# MCU_Board.net
KiCad netlist of a schematic drawn in Altium Designer
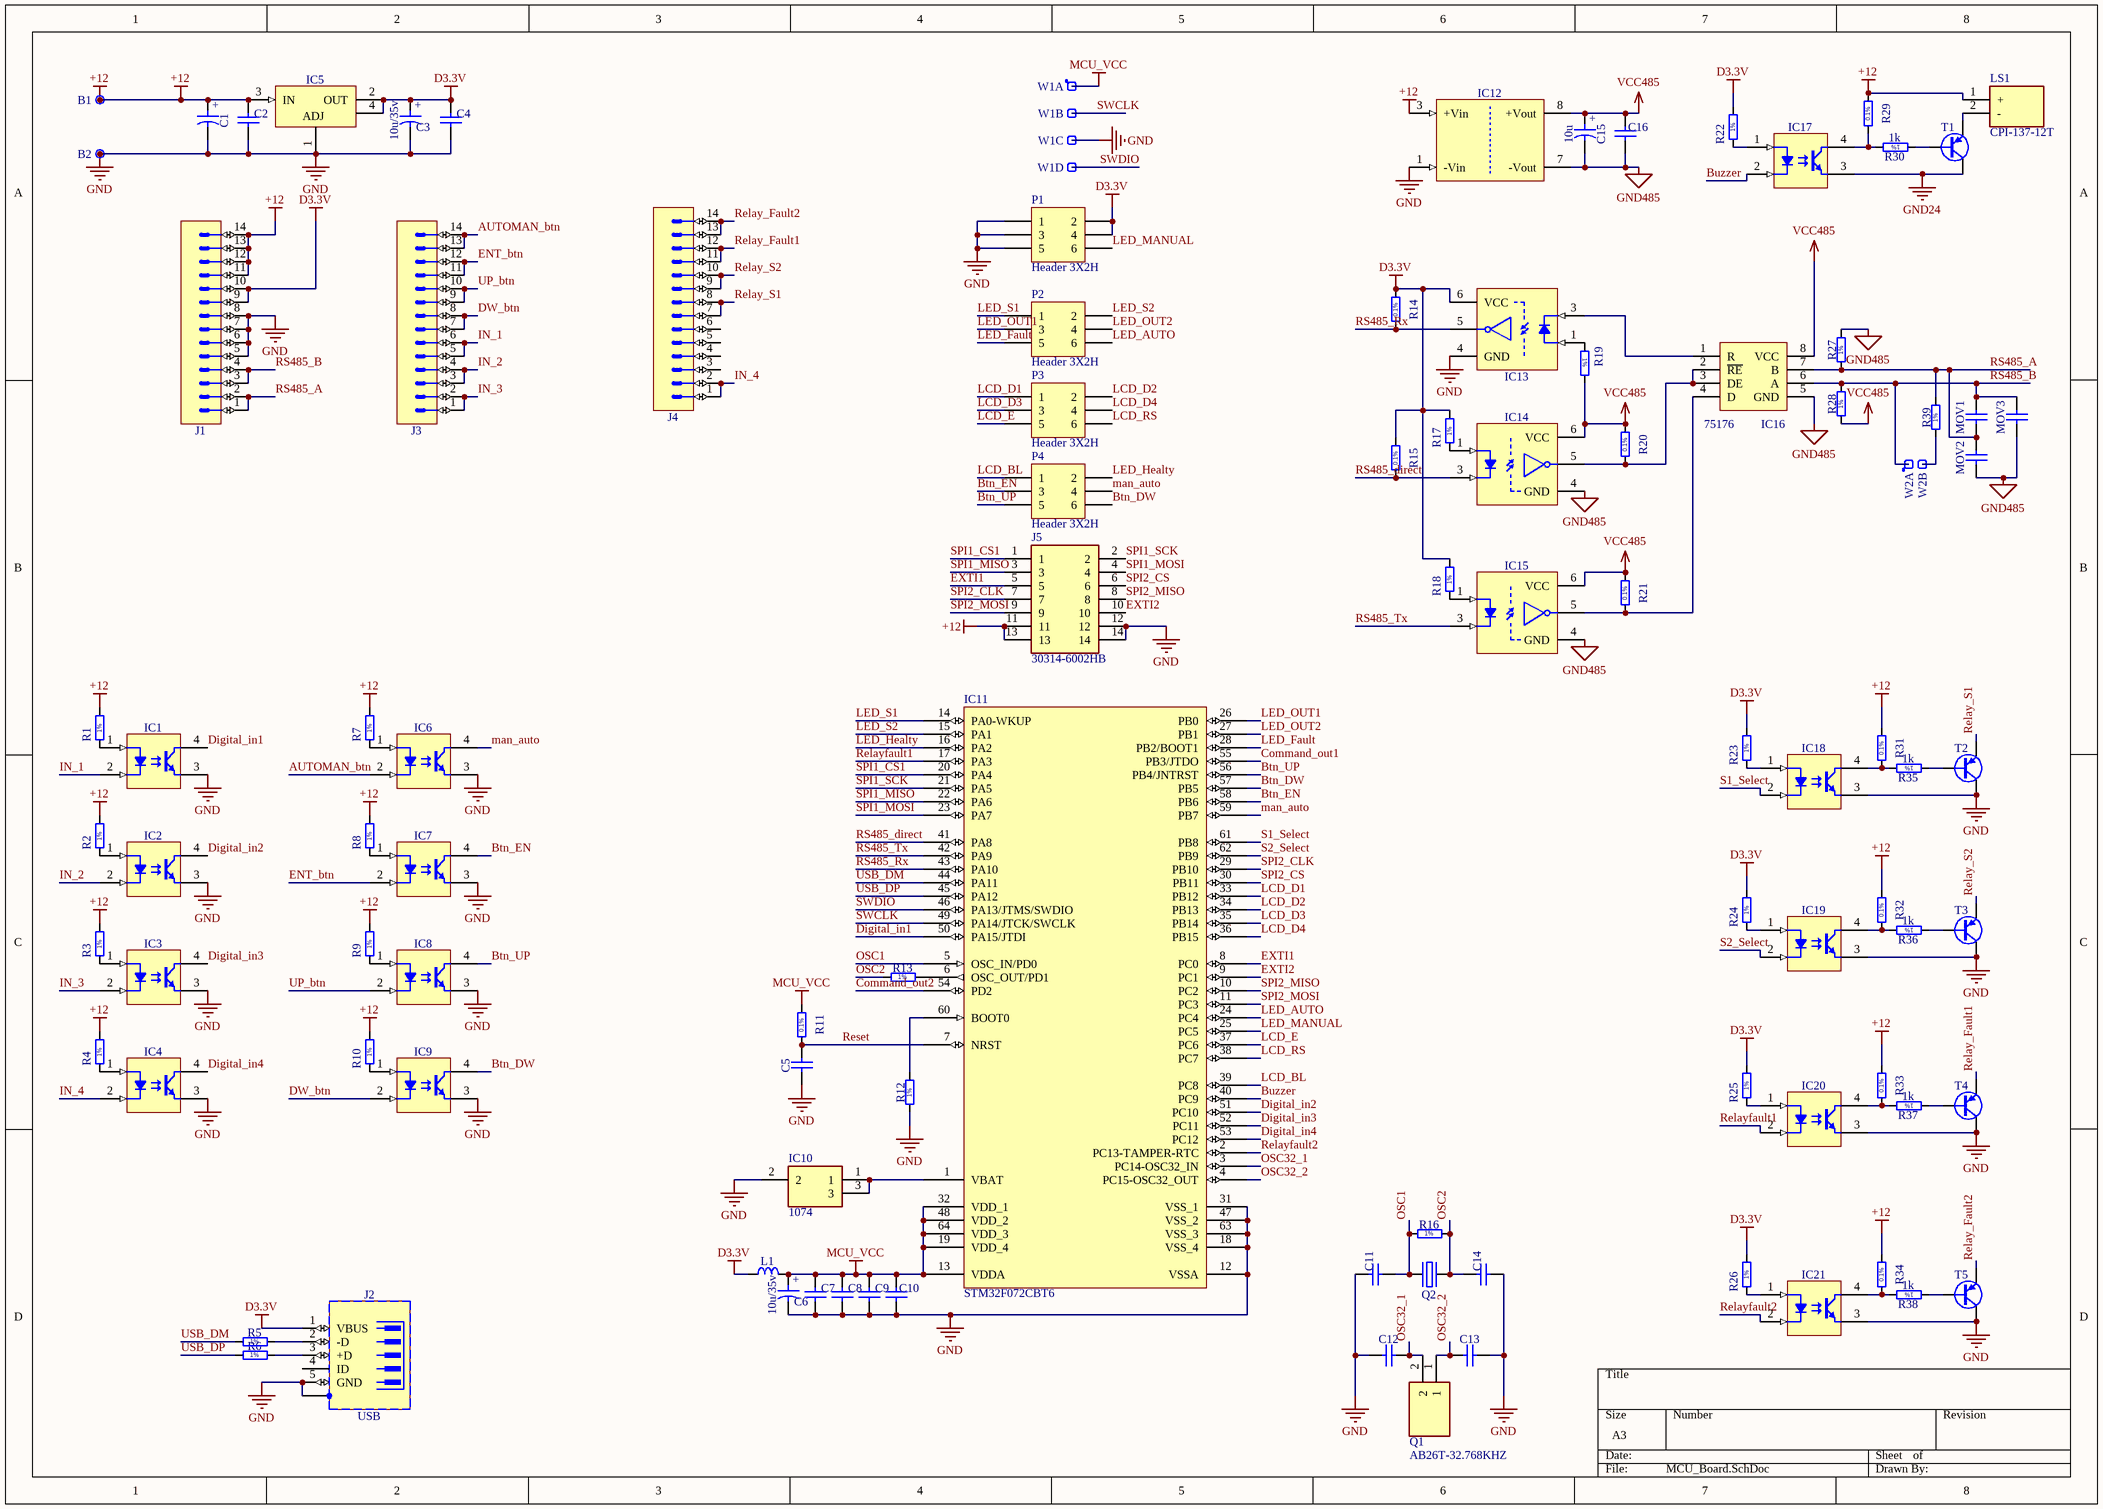
[diagram p0: MCU_Board.SchDoc]

(export (version "E")
  (design (tool "Eeschema 10.0.6"))
  (components
    (comp (ref "B1")
      (value "Plated Hole")
      (footprint "MTG240_400")
      (description "Single Terminal Socket")
      (fields (field (name "PART NUMBER") "PLATED_HOLE2.4_PAD4.0") (field (name "AUTHOR") "CERN DEM JMW"))
      (libsource (lib "Eletro-mechanical") (part "Single Terminal Socket"))
    )
    (comp (ref "B2")
      (value "Plated Hole")
      (footprint "MTG240_400")
      (description "Single Terminal Socket")
      (fields (field (name "PART NUMBER") "PLATED_HOLE2.4_PAD4.0") (field (name "AUTHOR") "CERN DEM JMW"))
      (libsource (lib "Eletro-mechanical") (part "Single Terminal Socket"))
    )
    (comp (ref "C1")
      (value "100uF")
      (footprint "CAPAE830X1020N")
      (description "Polarised capacitor")
      (fields
        (field (name "PART NUMBER") "CAE830-1020_100UF_35V_20%")
        (field (name "VOLTAGE") "35V")
        (field (name "AUTHOR") "CERN DEM JLC")
      )
      (libsource (lib "Capacitors") (part "Capacitor - polarized"))
    )
    (comp (ref "C2")
      (value "0.1uf")
      (footprint "CAPC2012X135N")
      (description "0092-0004-8")
      (fields
        (field (name "PART NUMBER") "CC0805_100NF_50V_10%_X7R")
        (field (name "VOLTAGE") "50V")
        (field (name "AUTHOR") "CERN DEM JLC")
      )
      (libsource (lib "Capacitors") (part "Capacitor - non polarized"))
    )
    (comp (ref "C3")
      (value "10u/35v")
      (footprint "CAPAE530X540N")
      (description "0289-0032-3")
      (fields
        (field (name "PART NUMBER") "CAE530-540_10UF_35V_20%")
        (field (name "VOLTAGE") "35V")
        (field (name "AUTHOR") "CERN DEM JLC")
      )
      (libsource (lib "Capacitors") (part "Capacitor - polarized"))
    )
    (comp (ref "C4")
      (value "0.1uf")
      (footprint "CAPC2012X135N")
      (description "0092-0004-8")
      (fields
        (field (name "PART NUMBER") "CC0805_100NF_50V_10%_X7R")
        (field (name "VOLTAGE") "50V")
        (field (name "AUTHOR") "CERN DEM JLC")
      )
      (libsource (lib "Capacitors") (part "Capacitor - non polarized"))
    )
    (comp (ref "C5")
      (value "0.1uf")
      (footprint "CAPC2012X135N")
      (description "0092-0004-8")
      (fields
        (field (name "PART NUMBER") "CC0805_100NF_50V_10%_X7R")
        (field (name "VOLTAGE") "50V")
        (field (name "AUTHOR") "CERN DEM JLC")
      )
      (libsource (lib "Capacitors") (part "Capacitor - non polarized"))
    )
    (comp (ref "C6")
      (value "10u/35v")
      (footprint "CAPAE530X540N")
      (description "0289-0032-3")
      (fields
        (field (name "PART NUMBER") "CAE530-540_10UF_35V_20%")
        (field (name "VOLTAGE") "35V")
        (field (name "AUTHOR") "CERN DEM JLC")
      )
      (libsource (lib "Capacitors") (part "Capacitor - polarized"))
    )
    (comp (ref "C7")
      (value "0.1uf")
      (footprint "CAPC2012X135N")
      (description "0092-0004-8")
      (fields
        (field (name "PART NUMBER") "CC0805_100NF_50V_10%_X7R")
        (field (name "VOLTAGE") "50V")
        (field (name "AUTHOR") "CERN DEM JLC")
      )
      (libsource (lib "Capacitors") (part "Capacitor - non polarized"))
    )
    (comp (ref "C8")
      (value "0.1uf")
      (footprint "CAPC2012X135N")
      (description "0092-0004-8")
      (fields
        (field (name "PART NUMBER") "CC0805_100NF_50V_10%_X7R")
        (field (name "VOLTAGE") "50V")
        (field (name "AUTHOR") "CERN DEM JLC")
      )
      (libsource (lib "Capacitors") (part "Capacitor - non polarized"))
    )
    (comp (ref "C9")
      (value "0.1uf")
      (footprint "CAPC2012X135N")
      (description "0092-0004-8")
      (fields
        (field (name "PART NUMBER") "CC0805_100NF_50V_10%_X7R")
        (field (name "VOLTAGE") "50V")
        (field (name "AUTHOR") "CERN DEM JLC")
      )
      (libsource (lib "Capacitors") (part "Capacitor - non polarized"))
    )
    (comp (ref "C10")
      (value "0.1uf")
      (footprint "CAPC2012X135N")
      (description "0092-0004-8")
      (fields
        (field (name "PART NUMBER") "CC0805_100NF_50V_10%_X7R")
        (field (name "VOLTAGE") "50V")
        (field (name "AUTHOR") "CERN DEM JLC")
      )
      (libsource (lib "Capacitors") (part "Capacitor - non polarized"))
    )
    (comp (ref "C11")
      (value "12pf")
      (footprint "CAPC2012X135N")
      (description "0306-0172-8")
      (fields
        (field (name "PART NUMBER") "CC0805_100NF_50V_10%_X7R")
        (field (name "VOLTAGE") "50V")
        (field (name "AUTHOR") "CERN DEM JLC")
      )
      (libsource (lib "Capacitors") (part "Capacitor - non polarized"))
    )
    (comp (ref "C12")
      (value "12pf")
      (footprint "CAPC2012X135N")
      (description "0306-0172-8")
      (fields
        (field (name "PART NUMBER") "CC0805_12PF_50V_5%_NP0")
        (field (name "VOLTAGE") "50V")
        (field (name "AUTHOR") "CERN DEM JLC")
      )
      (libsource (lib "Capacitors") (part "Capacitor - non polarized"))
    )
    (comp (ref "C13")
      (value "12pf")
      (footprint "CAPC2012X135N")
      (description "0306-0172-8")
      (fields
        (field (name "PART NUMBER") "CC0805_12PF_50V_5%_NP0")
        (field (name "VOLTAGE") "50V")
        (field (name "AUTHOR") "CERN DEM JLC")
      )
      (libsource (lib "Capacitors") (part "Capacitor - non polarized"))
    )
    (comp (ref "C14")
      (value "12pf")
      (footprint "CAPC2012X135N")
      (description "0306-0172-8")
      (fields
        (field (name "PART NUMBER") "CC0805_100NF_50V_10%_X7R")
        (field (name "VOLTAGE") "50V")
        (field (name "AUTHOR") "CERN DEM JLC")
      )
      (libsource (lib "Capacitors") (part "Capacitor - non polarized"))
    )
    (comp (ref "C15")
      (value "10u")
      (footprint "CAPAE430X540N")
      (description "0289-0167-5")
      (fields
        (field (name "PART NUMBER") "CAE430-540_10UF_16V_20%")
        (field (name "VOLTAGE") "16V")
        (field (name "AUTHOR") "CERN DEM JLC")
      )
      (libsource (lib "Capacitors") (part "Capacitor - polarized"))
    )
    (comp (ref "C16")
      (value "0.1uf")
      (footprint "CAPC2012X135N")
      (description "0092-0004-8")
      (fields
        (field (name "PART NUMBER") "CC0805_100NF_50V_10%_X7R")
        (field (name "VOLTAGE") "50V")
        (field (name "AUTHOR") "CERN DEM JLC")
      )
      (libsource (lib "Capacitors") (part "Capacitor - non polarized"))
    )
    (comp (ref "IC1")
      (value "PC817")
      (footprint "FAIRCHILD_FOD817DSD")
      (description "0084-0033-3")
      (fields
        (field (name "PART NUMBER") "FOD817DSD")
        (field (name "MANUFACTURER") "FAIRCHILD SEMICONDUCTOR")
        (field (name "AUTHOR") "CERN DEM JLC")
      )
      (libsource (lib "ICs And Semiconductors") (part "Optocoupler Type7"))
    )
    (comp (ref "IC2")
      (value "PC817")
      (footprint "FAIRCHILD_FOD817DSD")
      (description "0084-0033-3")
      (fields
        (field (name "PART NUMBER") "FOD817DSD")
        (field (name "MANUFACTURER") "FAIRCHILD SEMICONDUCTOR")
        (field (name "AUTHOR") "CERN DEM JLC")
      )
      (libsource (lib "ICs And Semiconductors") (part "Optocoupler Type7"))
    )
    (comp (ref "IC3")
      (value "PC817")
      (footprint "FAIRCHILD_FOD817DSD")
      (description "0084-0033-3")
      (fields
        (field (name "PART NUMBER") "FOD817DSD")
        (field (name "MANUFACTURER") "FAIRCHILD SEMICONDUCTOR")
        (field (name "AUTHOR") "CERN DEM JLC")
      )
      (libsource (lib "ICs And Semiconductors") (part "Optocoupler Type7"))
    )
    (comp (ref "IC4")
      (value "PC817")
      (footprint "FAIRCHILD_FOD817DSD")
      (description "0084-0033-3")
      (fields
        (field (name "PART NUMBER") "FOD817DSD")
        (field (name "MANUFACTURER") "FAIRCHILD SEMICONDUCTOR")
        (field (name "AUTHOR") "CERN DEM JLC")
      )
      (libsource (lib "ICs And Semiconductors") (part "Optocoupler Type7"))
    )
    (comp (ref "IC5")
      (value "LM1117MPX-3.3")
      (footprint "SOT230P700X180-4N")
      (description "0083-0491-4")
      (fields
        (field (name "PART NUMBER") "LM1117MPX-ADJ/NOPB")
        (field (name "MANUFACTURER") "NATIONAL SEMICONDUCTOR")
        (field (name "AUTHOR") "CERN DEM JLC")
      )
      (libsource (lib "ICs And Semiconductors") (part "REG3+1 1ADJ-2OUT-3IN+4OUT"))
    )
    (comp (ref "IC6")
      (value "PC817")
      (footprint "FAIRCHILD_FOD817DSD")
      (description "0084-0033-3")
      (fields
        (field (name "PART NUMBER") "FOD817DSD")
        (field (name "MANUFACTURER") "FAIRCHILD SEMICONDUCTOR")
        (field (name "AUTHOR") "CERN DEM JLC")
      )
      (libsource (lib "ICs And Semiconductors") (part "Optocoupler Type7"))
    )
    (comp (ref "IC7")
      (value "PC817")
      (footprint "FAIRCHILD_FOD817DSD")
      (description "0084-0033-3")
      (fields
        (field (name "PART NUMBER") "FOD817DSD")
        (field (name "MANUFACTURER") "FAIRCHILD SEMICONDUCTOR")
        (field (name "AUTHOR") "CERN DEM JLC")
      )
      (libsource (lib "ICs And Semiconductors") (part "Optocoupler Type7"))
    )
    (comp (ref "IC8")
      (value "PC817")
      (footprint "FAIRCHILD_FOD817DSD")
      (description "0084-0033-3")
      (fields
        (field (name "PART NUMBER") "FOD817DSD")
        (field (name "MANUFACTURER") "FAIRCHILD SEMICONDUCTOR")
        (field (name "AUTHOR") "CERN DEM JLC")
      )
      (libsource (lib "ICs And Semiconductors") (part "Optocoupler Type7"))
    )
    (comp (ref "IC9")
      (value "PC817")
      (footprint "FAIRCHILD_FOD817DSD")
      (description "0084-0033-3")
      (fields
        (field (name "PART NUMBER") "FOD817DSD")
        (field (name "MANUFACTURER") "FAIRCHILD SEMICONDUCTOR")
        (field (name "AUTHOR") "CERN DEM JLC")
      )
      (libsource (lib "ICs And Semiconductors") (part "Optocoupler Type7"))
    )
    (comp (ref "IC10")
      (value "1074")
      (footprint "SamacSys:1074")
      (description "Undefined or Miscellaneous")
      (fields (field (name "MOUSER2 PART NUMBER") "534-1074"))
      (libsource (lib "SamacSys") (part "1074"))
    )
    (comp (ref "IC11")
      (value "STM32F072CBT6")
      (footprint "LQFP64_N")
      (description "STM32 ARM-based 32-bit MCU with 64 Kbytes Flash, 64-pin LQFP, Industrial Temperature")
      (fields (field (name "PUBLISHER") "Altium Limited"))
      (libsource (lib "ST Microcontroller 32-Bit STM32") (part "STM32F103R8T6"))
    )
    (comp (ref "IC12")
      (value "TES 1-0511")
      (footprint "DCDC_TRACO_TES1-XX1X")
      (fields (field (name "MANUFACTURER") "TRACO POWER") (field (name "AUTHOR") "CERN DEM JMW"))
      (libsource (lib "ICs And Semiconductors") (part "DCDC_TRACO_TES1_Single Output"))
    )
    (comp (ref "IC13")
      (value "ACPL-W60L-000E")
      (footprint "SOIC127P1150X360-6N")
      (description "0087-0267-8")
      (fields (field (name "MANUFACTURER") "AVAGO TECHNOLOGIES") (field (name "AUTHOR") "CERN DEM JMW"))
      (libsource (lib "") (part "Optocoupler Type16_1"))
    )
    (comp (ref "IC14")
      (value "ACPL-W60L-000E")
      (footprint "SOIC127P1150X360-6N")
      (description "0087-0267-8")
      (fields (field (name "MANUFACTURER") "AVAGO TECHNOLOGIES") (field (name "AUTHOR") "CERN DEM JMW"))
      (libsource (lib "ICs And Semiconductors") (part "Optocoupler Type16"))
    )
    (comp (ref "IC15")
      (value "ACPL-W60L-000E")
      (footprint "SOIC127P1150X360-6N")
      (description "0087-0267-8")
      (fields (field (name "MANUFACTURER") "AVAGO TECHNOLOGIES") (field (name "AUTHOR") "CERN DEM JMW"))
      (libsource (lib "ICs And Semiconductors") (part "Optocoupler Type16"))
    )
    (comp (ref "IC16") (value "75176") (footprint "SO8_N") (libsource (lib "*") (part "SN75176")))
    (comp (ref "IC17")
      (value "PC817")
      (footprint "FAIRCHILD_FOD817DSD")
      (description "0084-0033-3")
      (fields
        (field (name "PART NUMBER") "FOD817DSD")
        (field (name "MANUFACTURER") "FAIRCHILD SEMICONDUCTOR")
        (field (name "AUTHOR") "CERN DEM JLC")
      )
      (libsource (lib "ICs And Semiconductors") (part "Optocoupler Type7"))
    )
    (comp (ref "IC18")
      (value "PC817")
      (footprint "FAIRCHILD_FOD817DSD")
      (description "0084-0033-3")
      (fields
        (field (name "PART NUMBER") "FOD817DSD")
        (field (name "MANUFACTURER") "FAIRCHILD SEMICONDUCTOR")
        (field (name "AUTHOR") "CERN DEM JLC")
      )
      (libsource (lib "ICs And Semiconductors") (part "Optocoupler Type7"))
    )
    (comp (ref "IC19")
      (value "PC817")
      (footprint "FAIRCHILD_FOD817DSD")
      (description "0084-0033-3")
      (fields
        (field (name "PART NUMBER") "FOD817DSD")
        (field (name "MANUFACTURER") "FAIRCHILD SEMICONDUCTOR")
        (field (name "AUTHOR") "CERN DEM JLC")
      )
      (libsource (lib "ICs And Semiconductors") (part "Optocoupler Type7"))
    )
    (comp (ref "IC20")
      (value "PC817")
      (footprint "FAIRCHILD_FOD817DSD")
      (description "0084-0033-3")
      (fields
        (field (name "PART NUMBER") "FOD817DSD")
        (field (name "MANUFACTURER") "FAIRCHILD SEMICONDUCTOR")
        (field (name "AUTHOR") "CERN DEM JLC")
      )
      (libsource (lib "ICs And Semiconductors") (part "Optocoupler Type7"))
    )
    (comp (ref "IC21")
      (value "PC817")
      (footprint "FAIRCHILD_FOD817DSD")
      (description "0084-0033-3")
      (fields
        (field (name "PART NUMBER") "FOD817DSD")
        (field (name "MANUFACTURER") "FAIRCHILD SEMICONDUCTOR")
        (field (name "AUTHOR") "CERN DEM JLC")
      )
      (libsource (lib "ICs And Semiconductors") (part "Optocoupler Type7"))
    )
    (comp (ref "J1")
      (value "Header 14")
      (footprint "STELVIO-KONTEK_3910401114400")
      (description "Connector 14 Male")
      (fields
        (field (name "PART NUMBER") "STELVIO-KONTEK_3910401114400")
        (field (name "MANUFACTURER") "STELVIO-KONTEK")
        (field (name "AUTHOR") "CERN DEM JLC")
      )
      (libsource (lib "Connectors") (part "Connector 14 Male"))
    )
    (comp (ref "J2")
      (value "USB")
      (footprint "TYCO_1734035-1")
      (description "5 Pin + 1 Shield USB Receptacle")
      (fields
        (field (name "PART NUMBER") "TYCO_1734035-1")
        (field (name "MANUFACTURER") "TYCO ELECTRONICS")
        (field (name "AUTHOR") "CERN DEM JLC")
      )
      (libsource (lib "Connectors") (part "Connector USB 5 Pin + 1Shield"))
    )
    (comp (ref "J3")
      (value "Header 14")
      (footprint "STELVIO-KONTEK_3910401114400")
      (description "Connector 14 Male")
      (fields
        (field (name "PART NUMBER") "STELVIO-KONTEK_3910401114400")
        (field (name "MANUFACTURER") "STELVIO-KONTEK")
        (field (name "AUTHOR") "CERN DEM JLC")
      )
      (libsource (lib "Connectors") (part "Connector 14 Male"))
    )
    (comp (ref "J4")
      (value "Header 14")
      (footprint "STELVIO-KONTEK_3910401114400")
      (description "Connector 14 Male")
      (fields
        (field (name "PART NUMBER") "STELVIO-KONTEK_3910401114400")
        (field (name "MANUFACTURER") "STELVIO-KONTEK")
        (field (name "AUTHOR") "CERN DEM JLC")
      )
      (libsource (lib "Connectors") (part "Connector 14 Male"))
    )
    (comp (ref "J5")
      (value "30314-6002HB")
      (footprint "SHDR14W64P254_2X7_2540X878X955P")
      (description "Connector")
      (libsource (lib "*") (part "30314-6002HB"))
    )
    (comp (ref "L1")
      (value "600")
      (footprint "INDC2012X105N")
      (description "0169-0010-4")
      (fields
        (field (name "PART NUMBER") "IND0805_MURATA_BLM21PG221SN1D")
        (field (name "POWER") "2A")
        (field (name "AUTHOR") "CERN DEM JLC")
      )
      (libsource (lib "Inductors & Transformers") (part "Inductor"))
    )
    (comp (ref "LS1")
      (value "CPI-137-12T")
      (footprint "SamacSys:CPI13712T")
      (description "Loudspeaker or Buzzer")
      (libsource (lib "SamacSys") (part "CPI-137-12T"))
    )
    (comp (ref "MOV1")
      (value "10nF")
      (footprint "CAPR500-300X720X650")
      (description "0221-0014-7")
      (fields
        (field (name "PART NUMBER") "CPER_10NF_400V_10%_500-300X720X650")
        (field (name "VOLTAGE") "400VDC/200VAC")
        (field (name "AUTHOR") "CERN DEM JLC")
      )
      (libsource (lib "Capacitors") (part "Capacitor - non polarized"))
    )
    (comp (ref "MOV2")
      (value "10nF")
      (footprint "CAPR500-300X720X650")
      (description "0221-0014-7")
      (fields
        (field (name "PART NUMBER") "CPER_10NF_400V_10%_500-300X720X650")
        (field (name "VOLTAGE") "400VDC/200VAC")
        (field (name "AUTHOR") "CERN DEM JLC")
      )
      (libsource (lib "Capacitors") (part "Capacitor - non polarized"))
    )
    (comp (ref "MOV3")
      (value "10nF")
      (footprint "CAPR500-300X720X650")
      (description "0221-0014-7")
      (fields
        (field (name "PART NUMBER") "CPER_10NF_400V_10%_500-300X720X650")
        (field (name "VOLTAGE") "400VDC/200VAC")
        (field (name "AUTHOR") "CERN DEM JLC")
      )
      (libsource (lib "Capacitors") (part "Capacitor - non polarized"))
    )
    (comp (ref "P1")
      (value "Header 3X2H")
      (footprint "HDR2X3H")
      (description "Header, 3-Pin, Dual row, Right Angle")
      (fields (field (name "PUBLISHER") "Altium Limited"))
      (libsource (lib "Miscellaneous Connectors") (part "Header 3X2H"))
    )
    (comp (ref "P2")
      (value "Header 3X2H")
      (footprint "HDR2X3H")
      (description "Header, 3-Pin, Dual row, Right Angle")
      (fields (field (name "PUBLISHER") "Altium Limited"))
      (libsource (lib "Miscellaneous Connectors") (part "Header 3X2H"))
    )
    (comp (ref "P3")
      (value "Header 3X2H")
      (footprint "HDR2X3H")
      (description "Header, 3-Pin, Dual row, Right Angle")
      (fields (field (name "PUBLISHER") "Altium Limited"))
      (libsource (lib "Miscellaneous Connectors") (part "Header 3X2H"))
    )
    (comp (ref "P4")
      (value "Header 3X2H")
      (footprint "HDR2X3H")
      (description "Header, 3-Pin, Dual row, Right Angle")
      (fields (field (name "PUBLISHER") "Altium Limited"))
      (libsource (lib "Miscellaneous Connectors") (part "Header 3X2H"))
    )
    (comp (ref "Q1")
      (value "AB26T-32.768KHZ")
      (footprint "SamacSys:AB26T")
      (description "Crystal or Oscillator")
      (libsource (lib "SamacSys") (part "AB26T-32.768KHZ"))
    )
    (comp (ref "Q2")
      (value "8.192Mhz")
      (footprint "XTAL1160X490X430")
      (description "No E -source")
      (fields
        (field (name "PART NUMBER") "XTAL_6MHZ_RAKON_HC49/4H SMX_20/50/10/16")
        (field (name "MANUFACTURER") "RAKON")
        (field (name "AUTHOR") "CERN DEM JMW")
      )
      (libsource (lib "ICs And Semiconductors") (part "Quartz Crystal"))
    )
    (comp (ref "R1")
      (value "330")
      (footprint "RESC2012X60N")
      (description "0150-3297-4")
      (fields
        (field (name "PART NUMBER") "R0805_330R_1%_0.125W_100PPM")
        (field (name "POWER") "0.125W")
        (field (name "AUTHOR") "CERN DEM JLC")
      )
      (libsource (lib "Resistors") (part "Resistor - 1%"))
    )
    (comp (ref "R2")
      (value "330")
      (footprint "RESC2012X60N")
      (description "0150-3297-4")
      (fields
        (field (name "PART NUMBER") "R0805_330R_1%_0.125W_100PPM")
        (field (name "POWER") "0.125W")
        (field (name "AUTHOR") "CERN DEM JLC")
      )
      (libsource (lib "Resistors") (part "Resistor - 1%"))
    )
    (comp (ref "R3")
      (value "330")
      (footprint "RESC2012X60N")
      (description "0150-3297-4")
      (fields
        (field (name "PART NUMBER") "R0805_330R_1%_0.125W_100PPM")
        (field (name "POWER") "0.125W")
        (field (name "AUTHOR") "CERN DEM JLC")
      )
      (libsource (lib "Resistors") (part "Resistor - 1%"))
    )
    (comp (ref "R4")
      (value "330")
      (footprint "RESC2012X60N")
      (description "0150-3297-4")
      (fields
        (field (name "PART NUMBER") "R0805_330R_1%_0.125W_100PPM")
        (field (name "POWER") "0.125W")
        (field (name "AUTHOR") "CERN DEM JLC")
      )
      (libsource (lib "Resistors") (part "Resistor - 1%"))
    )
    (comp (ref "R5")
      (value "27")
      (footprint "RESC2012X60N")
      (description "Resistor - 1%")
      (fields
        (field (name "PART NUMBER") "R0805_27R_1%_0.125W_100PPM")
        (field (name "POWER") "0.125W")
        (field (name "AUTHOR") "CERN DEM JLC")
      )
      (libsource (lib "Resistors") (part "Resistor - 1%"))
    )
    (comp (ref "R6")
      (value "27")
      (footprint "RESC2012X60N")
      (description "Resistor - 1%")
      (fields
        (field (name "PART NUMBER") "R0805_27R_1%_0.125W_100PPM")
        (field (name "POWER") "0.125W")
        (field (name "AUTHOR") "CERN DEM JLC")
      )
      (libsource (lib "Resistors") (part "Resistor - 1%"))
    )
    (comp (ref "R7")
      (value "330")
      (footprint "RESC2012X60N")
      (description "0150-3297-4")
      (fields
        (field (name "PART NUMBER") "R0805_330R_1%_0.125W_100PPM")
        (field (name "POWER") "0.125W")
        (field (name "AUTHOR") "CERN DEM JLC")
      )
      (libsource (lib "Resistors") (part "Resistor - 1%"))
    )
    (comp (ref "R8")
      (value "330")
      (footprint "RESC2012X60N")
      (description "0150-3297-4")
      (fields
        (field (name "PART NUMBER") "R0805_330R_1%_0.125W_100PPM")
        (field (name "POWER") "0.125W")
        (field (name "AUTHOR") "CERN DEM JLC")
      )
      (libsource (lib "Resistors") (part "Resistor - 1%"))
    )
    (comp (ref "R9")
      (value "330")
      (footprint "RESC2012X60N")
      (description "0150-3297-4")
      (fields
        (field (name "PART NUMBER") "R0805_330R_1%_0.125W_100PPM")
        (field (name "POWER") "0.125W")
        (field (name "AUTHOR") "CERN DEM JLC")
      )
      (libsource (lib "Resistors") (part "Resistor - 1%"))
    )
    (comp (ref "R10")
      (value "330")
      (footprint "RESC2012X60N")
      (description "0150-3297-4")
      (fields
        (field (name "PART NUMBER") "R0805_330R_1%_0.125W_100PPM")
        (field (name "POWER") "0.125W")
        (field (name "AUTHOR") "CERN DEM JLC")
      )
      (libsource (lib "Resistors") (part "Resistor - 1%"))
    )
    (comp (ref "R11")
      (value "10k")
      (footprint "RESC2012X60N")
      (description "0176-0426-3")
      (fields
        (field (name "PART NUMBER") "R0805_10K_0.1%_0.1W_10PPM")
        (field (name "POWER") "0.1W")
        (field (name "AUTHOR") "CERN DEM JLC")
      )
      (libsource (lib "Resistors") (part "Resistor - 0.1%"))
    )
    (comp (ref "R12")
      (value "510")
      (footprint "RESC2012X60N")
      (description "Resistor - 1%")
      (fields
        (field (name "PART NUMBER") "R0805_510R_1%_0.125W_100PPM")
        (field (name "POWER") "0.125W")
        (field (name "AUTHOR") "CERN DEM JLC")
      )
      (libsource (lib "Resistors") (part "Resistor - 1%"))
    )
    (comp (ref "R13")
      (value "220")
      (footprint "RESC2012X60N")
      (description "Resistor - 1%")
      (fields
        (field (name "PART NUMBER") "R0805_220R_1%_0.125W_100PPM")
        (field (name "POWER") "0.125W")
        (field (name "AUTHOR") "CERN DEM JLC")
      )
      (libsource (lib "Resistors") (part "Resistor - 1%"))
    )
    (comp (ref "R14")
      (value "10k")
      (footprint "RESC2012X60N")
      (description "0176-0426-3")
      (fields
        (field (name "PART NUMBER") "R0805_10K_0.1%_0.1W_10PPM")
        (field (name "POWER") "0.1W")
        (field (name "AUTHOR") "CERN DEM JLC")
      )
      (libsource (lib "Resistors") (part "Resistor - 0.1%"))
    )
    (comp (ref "R15")
      (value "10k")
      (footprint "RESC2012X60N")
      (description "0176-0426-3")
      (fields
        (field (name "PART NUMBER") "R0805_10K_0.1%_0.1W_10PPM")
        (field (name "POWER") "0.1W")
        (field (name "AUTHOR") "CERN DEM JLC")
      )
      (libsource (lib "Resistors") (part "Resistor - 0.1%"))
    )
    (comp (ref "R16")
      (value "1M")
      (footprint "RESC2012X60N")
      (description "Resistor - 1%")
      (fields
        (field (name "PART NUMBER") "R0805_1M_1%_0.125W_100PPM")
        (field (name "POWER") "0.125W")
        (field (name "AUTHOR") "CERN DEM JLC")
      )
      (libsource (lib "Resistors") (part "Resistor - 1%"))
    )
    (comp (ref "R17")
      (value "330")
      (footprint "RESC2012X60N")
      (description "0150-3297-4")
      (fields
        (field (name "PART NUMBER") "R0805_330R_1%_0.125W_100PPM")
        (field (name "POWER") "0.125W")
        (field (name "AUTHOR") "CERN DEM JLC")
      )
      (libsource (lib "Resistors") (part "Resistor - 1%"))
    )
    (comp (ref "R18")
      (value "330")
      (footprint "RESC2012X60N")
      (description "0150-3297-4")
      (fields
        (field (name "PART NUMBER") "R0805_330R_1%_0.125W_100PPM")
        (field (name "POWER") "0.125W")
        (field (name "AUTHOR") "CERN DEM JLC")
      )
      (libsource (lib "Resistors") (part "Resistor - 1%"))
    )
    (comp (ref "R19")
      (value "330")
      (footprint "RESC2012X60N")
      (description "0150-3297-4")
      (fields
        (field (name "PART NUMBER") "R0805_330R_1%_0.125W_100PPM")
        (field (name "POWER") "0.125W")
        (field (name "AUTHOR") "CERN DEM JLC")
      )
      (libsource (lib "Resistors") (part "Resistor - 1%"))
    )
    (comp (ref "R20")
      (value "10k")
      (footprint "RESC2012X60N")
      (description "0176-0426-3")
      (fields
        (field (name "PART NUMBER") "R0805_10K_0.1%_0.1W_10PPM")
        (field (name "POWER") "0.1W")
        (field (name "AUTHOR") "CERN DEM JLC")
      )
      (libsource (lib "Resistors") (part "Resistor - 0.1%"))
    )
    (comp (ref "R21")
      (value "10k")
      (footprint "RESC2012X60N")
      (description "0176-0426-3")
      (fields
        (field (name "PART NUMBER") "R0805_10K_0.1%_0.1W_10PPM")
        (field (name "POWER") "0.1W")
        (field (name "AUTHOR") "CERN DEM JLC")
      )
      (libsource (lib "Resistors") (part "Resistor - 0.1%"))
    )
    (comp (ref "R22")
      (value "330")
      (footprint "RESC2012X60N")
      (description "0150-3297-4")
      (fields
        (field (name "PART NUMBER") "R0805_330R_1%_0.125W_100PPM")
        (field (name "POWER") "0.125W")
        (field (name "AUTHOR") "CERN DEM JLC")
      )
      (libsource (lib "Resistors") (part "Resistor - 1%"))
    )
    (comp (ref "R23")
      (value "330")
      (footprint "RESC2012X60N")
      (description "0150-3297-4")
      (fields
        (field (name "PART NUMBER") "R0805_330R_1%_0.125W_100PPM")
        (field (name "POWER") "0.125W")
        (field (name "AUTHOR") "CERN DEM JLC")
      )
      (libsource (lib "Resistors") (part "Resistor - 1%"))
    )
    (comp (ref "R24")
      (value "330")
      (footprint "RESC2012X60N")
      (description "0150-3297-4")
      (fields
        (field (name "PART NUMBER") "R0805_330R_1%_0.125W_100PPM")
        (field (name "POWER") "0.125W")
        (field (name "AUTHOR") "CERN DEM JLC")
      )
      (libsource (lib "Resistors") (part "Resistor - 1%"))
    )
    (comp (ref "R25")
      (value "330")
      (footprint "RESC2012X60N")
      (description "0150-3297-4")
      (fields
        (field (name "PART NUMBER") "R0805_330R_1%_0.125W_100PPM")
        (field (name "POWER") "0.125W")
        (field (name "AUTHOR") "CERN DEM JLC")
      )
      (libsource (lib "Resistors") (part "Resistor - 1%"))
    )
    (comp (ref "R26")
      (value "330")
      (footprint "RESC2012X60N")
      (description "0150-3297-4")
      (fields
        (field (name "PART NUMBER") "R0805_330R_1%_0.125W_100PPM")
        (field (name "POWER") "0.125W")
        (field (name "AUTHOR") "CERN DEM JLC")
      )
      (libsource (lib "Resistors") (part "Resistor - 1%"))
    )
    (comp (ref "R27")
      (value "20k")
      (footprint "RESC2012X60N")
      (description "0176-0560-6")
      (fields
        (field (name "PART NUMBER") "R0805_20K_1%_0.125W_100PPM")
        (field (name "POWER") "0.125W")
        (field (name "AUTHOR") "CERN DEM JLC")
      )
      (libsource (lib "Resistors") (part "Resistor - 1%"))
    )
    (comp (ref "R28")
      (value "20k")
      (footprint "RESC2012X60N")
      (description "0176-0560-6")
      (fields
        (field (name "PART NUMBER") "R0805_20K_1%_0.125W_100PPM")
        (field (name "POWER") "0.125W")
        (field (name "AUTHOR") "CERN DEM JLC")
      )
      (libsource (lib "Resistors") (part "Resistor - 1%"))
    )
    (comp (ref "R29")
      (value "10k")
      (footprint "RESC2012X60N")
      (description "0176-0426-3")
      (fields
        (field (name "PART NUMBER") "R0805_10K_0.1%_0.1W_10PPM")
        (field (name "POWER") "0.1W")
        (field (name "AUTHOR") "CERN DEM JLC")
      )
      (libsource (lib "Resistors") (part "Resistor - 0.1%"))
    )
    (comp (ref "R30")
      (value "1k")
      (footprint "RESC2012X60N")
      (description "0176-0313-5")
      (fields
        (field (name "PART NUMBER") "R0805_1K_1%_0.125W_100PPM")
        (field (name "POWER") "0.125W")
        (field (name "AUTHOR") "CERN DEM JLC")
      )
      (libsource (lib "Resistors") (part "Resistor - 1%"))
    )
    (comp (ref "R31")
      (value "10k")
      (footprint "RESC2012X60N")
      (description "0176-0426-3")
      (fields
        (field (name "PART NUMBER") "R0805_10K_0.1%_0.1W_10PPM")
        (field (name "POWER") "0.1W")
        (field (name "AUTHOR") "CERN DEM JLC")
      )
      (libsource (lib "Resistors") (part "Resistor - 0.1%"))
    )
    (comp (ref "R32")
      (value "10k")
      (footprint "RESC2012X60N")
      (description "0176-0426-3")
      (fields
        (field (name "PART NUMBER") "R0805_10K_0.1%_0.1W_10PPM")
        (field (name "POWER") "0.1W")
        (field (name "AUTHOR") "CERN DEM JLC")
      )
      (libsource (lib "Resistors") (part "Resistor - 0.1%"))
    )
    (comp (ref "R33")
      (value "10k")
      (footprint "RESC2012X60N")
      (description "0176-0426-3")
      (fields
        (field (name "PART NUMBER") "R0805_10K_0.1%_0.1W_10PPM")
        (field (name "POWER") "0.1W")
        (field (name "AUTHOR") "CERN DEM JLC")
      )
      (libsource (lib "Resistors") (part "Resistor - 0.1%"))
    )
    (comp (ref "R34")
      (value "10k")
      (footprint "RESC2012X60N")
      (description "0176-0426-3")
      (fields
        (field (name "PART NUMBER") "R0805_10K_0.1%_0.1W_10PPM")
        (field (name "POWER") "0.1W")
        (field (name "AUTHOR") "CERN DEM JLC")
      )
      (libsource (lib "Resistors") (part "Resistor - 0.1%"))
    )
    (comp (ref "R35")
      (value "1k")
      (footprint "RESC2012X60N")
      (description "0176-0313-5")
      (fields
        (field (name "PART NUMBER") "R0805_1K_1%_0.125W_100PPM")
        (field (name "POWER") "0.125W")
        (field (name "AUTHOR") "CERN DEM JLC")
      )
      (libsource (lib "Resistors") (part "Resistor - 1%"))
    )
    (comp (ref "R36")
      (value "1k")
      (footprint "RESC2012X60N")
      (description "0176-0313-5")
      (fields
        (field (name "PART NUMBER") "R0805_1K_1%_0.125W_100PPM")
        (field (name "POWER") "0.125W")
        (field (name "AUTHOR") "CERN DEM JLC")
      )
      (libsource (lib "Resistors") (part "Resistor - 1%"))
    )
    (comp (ref "R37")
      (value "1k")
      (footprint "RESC2012X60N")
      (description "0176-0313-5")
      (fields
        (field (name "PART NUMBER") "R0805_1K_1%_0.125W_100PPM")
        (field (name "POWER") "0.125W")
        (field (name "AUTHOR") "CERN DEM JLC")
      )
      (libsource (lib "Resistors") (part "Resistor - 1%"))
    )
    (comp (ref "R38")
      (value "1k")
      (footprint "RESC2012X60N")
      (description "0176-0313-5")
      (fields
        (field (name "PART NUMBER") "R0805_1K_1%_0.125W_100PPM")
        (field (name "POWER") "0.125W")
        (field (name "AUTHOR") "CERN DEM JLC")
      )
      (libsource (lib "Resistors") (part "Resistor - 1%"))
    )
    (comp (ref "R39")
      (value "120")
      (footprint "RESC1608X55N")
      (description "0150-2451-4")
      (fields
        (field (name "PART NUMBER") "R0603_120R_1%_0.1W_100PPM")
        (field (name "POWER") "0.1W")
        (field (name "AUTHOR") "CERN DEM JLC")
      )
      (libsource (lib "Resistors") (part "Resistor - 1%"))
    )
    (comp (ref "T1")
      (value "MMBT3906LT1G")
      (footprint "SOT95P240X110-3N")
      (description "0235-0223-4")
      (fields
        (field (name "PART NUMBER") "BSR18A")
        (field (name "MANUFACTURER") "FAIRCHILD SEMICONDUCTOR")
        (field (name "AUTHOR") "CERN DEM JLC")
      )
      (libsource (lib "ICs And Semiconductors") (part "PNP B1 E2 C3"))
    )
    (comp (ref "T2")
      (value "MMBT3906LT1G")
      (footprint "SOT95P240X110-3N")
      (description "0235-0223-4")
      (fields
        (field (name "PART NUMBER") "BSR18A")
        (field (name "MANUFACTURER") "FAIRCHILD SEMICONDUCTOR")
        (field (name "AUTHOR") "CERN DEM JLC")
      )
      (libsource (lib "ICs And Semiconductors") (part "PNP B1 E2 C3"))
    )
    (comp (ref "T3")
      (value "MMBT3906LT1G")
      (footprint "SOT95P240X110-3N")
      (description "0235-0223-4")
      (fields
        (field (name "PART NUMBER") "BSR18A")
        (field (name "MANUFACTURER") "FAIRCHILD SEMICONDUCTOR")
        (field (name "AUTHOR") "CERN DEM JLC")
      )
      (libsource (lib "ICs And Semiconductors") (part "PNP B1 E2 C3"))
    )
    (comp (ref "T4")
      (value "MMBT3906LT1G")
      (footprint "SOT95P240X110-3N")
      (description "0235-0223-4")
      (fields
        (field (name "PART NUMBER") "BSR18A")
        (field (name "MANUFACTURER") "FAIRCHILD SEMICONDUCTOR")
        (field (name "AUTHOR") "CERN DEM JLC")
      )
      (libsource (lib "ICs And Semiconductors") (part "PNP B1 E2 C3"))
    )
    (comp (ref "T5")
      (value "MMBT3906LT1G")
      (footprint "SOT95P240X110-3N")
      (description "0235-0223-4")
      (fields
        (field (name "PART NUMBER") "BSR18A")
        (field (name "MANUFACTURER") "FAIRCHILD SEMICONDUCTOR")
        (field (name "AUTHOR") "CERN DEM JLC")
      )
      (libsource (lib "ICs And Semiconductors") (part "PNP B1 E2 C3"))
    )
    (comp (ref "W1")
      (value "Test Point")
      (footprint "COMATEL_385.0358.1.04.400")
      (description "4 Mini Wire-Wrap Contact Strip Header")
      (fields
        (field (name "PART NUMBER") "COMATEL_385.0358.1.04.400")
        (field (name "MANUFACTURER") "KONTEK COMATEL")
        (field (name "AUTHOR") "CERN DEM JLC")
      )
      (libsource (lib "Connectors") (part "Wire-Wrap Contact x4"))
    )
    (comp (ref "W2")
      (value "Test Point")
      (footprint "COMATEL_386.0358.1.02.440")
      (description "2 Mini Wire-Wrap Contact Strip Header")
      (fields
        (field (name "PART NUMBER") "COMATEL_386.0358.1.02.440")
        (field (name "MANUFACTURER") "KONTEK COMATEL")
        (field (name "AUTHOR") "CERN DEM JLC")
      )
      (libsource (lib "Connectors") (part "Wire-Wrap Contact x2"))
    )
  )
  (nets
    (net (code "1") (name "+12") (class "Default")
      (node (ref "B1") (pin "1") (pinfunction "1_1") (pintype "bidirectional"))
      (node (ref "C1") (pin "1") (pinfunction "1_1") (pintype "passive"))
      (node (ref "C2") (pin "1") (pinfunction "1_1") (pintype "passive"))
      (node (ref "IC12") (pin "3") (pinfunction "+Vin_3") (pintype "input"))
      (node (ref "IC5") (pin "3") (pinfunction "IN_3") (pintype "input"))
      (node (ref "J1") (pin "11") (pinfunction "11_11") (pintype "bidirectional"))
      (node (ref "J1") (pin "12") (pinfunction "12_12") (pintype "bidirectional"))
      (node (ref "J1") (pin "13") (pinfunction "13_13") (pintype "bidirectional"))
      (node (ref "J1") (pin "14") (pinfunction "14_14") (pintype "bidirectional"))
      (node (ref "J5") (pin "11") (pinfunction "11_11") (pintype "passive"))
      (node (ref "J5") (pin "13") (pinfunction "13_13") (pintype "passive"))
      (node (ref "LS1") (pin "1") (pinfunction "+_1") (pintype "passive"))
      (node (ref "R1") (pin "2") (pinfunction "2_2") (pintype "passive"))
      (node (ref "R10") (pin "2") (pinfunction "2_2") (pintype "passive"))
      (node (ref "R2") (pin "2") (pinfunction "2_2") (pintype "passive"))
      (node (ref "R29") (pin "2") (pinfunction "2_2") (pintype "passive"))
      (node (ref "R3") (pin "2") (pinfunction "2_2") (pintype "passive"))
      (node (ref "R31") (pin "2") (pinfunction "2_2") (pintype "passive"))
      (node (ref "R32") (pin "2") (pinfunction "2_2") (pintype "passive"))
      (node (ref "R33") (pin "2") (pinfunction "2_2") (pintype "passive"))
      (node (ref "R34") (pin "2") (pinfunction "2_2") (pintype "passive"))
      (node (ref "R4") (pin "2") (pinfunction "2_2") (pintype "passive"))
      (node (ref "R7") (pin "2") (pinfunction "2_2") (pintype "passive"))
      (node (ref "R8") (pin "2") (pinfunction "2_2") (pintype "passive"))
      (node (ref "R9") (pin "2") (pinfunction "2_2") (pintype "passive"))
    )
    (net (code "2") (name "/AUTOMAN_btn") (class "Default")
      (node (ref "IC6") (pin "2") (pinfunction "C_2") (pintype "input"))
      (node (ref "J3") (pin "13") (pinfunction "13_13") (pintype "bidirectional"))
      (node (ref "J3") (pin "14") (pinfunction "14_14") (pintype "bidirectional"))
    )
    (net (code "3") (name "/Btn_DW") (class "Default")
      (node (ref "IC11") (pin "57") (pinfunction "PB5_57") (pintype "bidirectional"))
      (node (ref "IC9") (pin "4") (pinfunction "C_4") (pintype "open_collector"))
      (node (ref "P4") (pin "6") (pinfunction "6_6") (pintype "passive"))
    )
    (net (code "4") (name "/Btn_EN") (class "Default")
      (node (ref "IC11") (pin "58") (pinfunction "PB6_58") (pintype "bidirectional"))
      (node (ref "IC7") (pin "4") (pinfunction "C_4") (pintype "open_collector"))
      (node (ref "P4") (pin "3") (pinfunction "3_3") (pintype "passive"))
    )
    (net (code "5") (name "/Btn_UP") (class "Default")
      (node (ref "IC11") (pin "56") (pinfunction "PB4/JNTRST_56") (pintype "bidirectional"))
      (node (ref "IC8") (pin "4") (pinfunction "C_4") (pintype "open_collector"))
      (node (ref "P4") (pin "5") (pinfunction "5_5") (pintype "passive"))
    )
    (net (code "6") (name "/Buzzer") (class "Default")
      (node (ref "IC11") (pin "40") (pinfunction "PC9_40") (pintype "bidirectional"))
      (node (ref "IC17") (pin "2") (pinfunction "C_2") (pintype "input"))
    )
    (net (code "7") (name "/Command_out1") (class "Default")
      (node (ref "IC11") (pin "55") (pinfunction "PB3/JTDO_55") (pintype "bidirectional"))
    )
    (net (code "8") (name "/Command_out2") (class "Default")
      (node (ref "IC11") (pin "54") (pinfunction "PD2_54") (pintype "bidirectional"))
    )
    (net (code "9") (name "/DW_btn") (class "Default")
      (node (ref "IC9") (pin "2") (pinfunction "C_2") (pintype "input"))
      (node (ref "J3") (pin "7") (pinfunction "7_7") (pintype "bidirectional"))
      (node (ref "J3") (pin "8") (pinfunction "8_8") (pintype "bidirectional"))
    )
    (net (code "10") (name "/Digital_in1") (class "Default")
      (node (ref "IC1") (pin "4") (pinfunction "C_4") (pintype "open_collector"))
      (node (ref "IC11") (pin "50") (pinfunction "PA15/JTDI_50") (pintype "bidirectional"))
    )
    (net (code "11") (name "/Digital_in2") (class "Default")
      (node (ref "IC11") (pin "51") (pinfunction "PC10_51") (pintype "bidirectional"))
      (node (ref "IC2") (pin "4") (pinfunction "C_4") (pintype "open_collector"))
    )
    (net (code "12") (name "/Digital_in3") (class "Default")
      (node (ref "IC11") (pin "52") (pinfunction "PC11_52") (pintype "bidirectional"))
      (node (ref "IC3") (pin "4") (pinfunction "C_4") (pintype "open_collector"))
    )
    (net (code "13") (name "/Digital_in4") (class "Default")
      (node (ref "IC11") (pin "53") (pinfunction "PC12_53") (pintype "bidirectional"))
      (node (ref "IC4") (pin "4") (pinfunction "C_4") (pintype "open_collector"))
    )
    (net (code "14") (name "/ENT_btn") (class "Default")
      (node (ref "IC7") (pin "2") (pinfunction "C_2") (pintype "input"))
      (node (ref "J3") (pin "11") (pinfunction "11_11") (pintype "bidirectional"))
      (node (ref "J3") (pin "12") (pinfunction "12_12") (pintype "bidirectional"))
    )
    (net (code "15") (name "/EXTI1") (class "Default")
      (node (ref "IC11") (pin "8") (pinfunction "PC0_8") (pintype "bidirectional"))
      (node (ref "J5") (pin "5") (pinfunction "5_5") (pintype "passive"))
    )
    (net (code "16") (name "/EXTI2") (class "Default")
      (node (ref "IC11") (pin "9") (pinfunction "PC1_9") (pintype "bidirectional"))
      (node (ref "J5") (pin "10") (pinfunction "10_10") (pintype "passive"))
    )
    (net (code "17") (name "/IN_1") (class "Default")
      (node (ref "IC1") (pin "2") (pinfunction "C_2") (pintype "input"))
      (node (ref "J3") (pin "5") (pinfunction "5_5") (pintype "bidirectional"))
      (node (ref "J3") (pin "6") (pinfunction "6_6") (pintype "bidirectional"))
    )
    (net (code "18") (name "/IN_2") (class "Default")
      (node (ref "IC2") (pin "2") (pinfunction "C_2") (pintype "input"))
      (node (ref "J3") (pin "3") (pinfunction "3_3") (pintype "bidirectional"))
      (node (ref "J3") (pin "4") (pinfunction "4_4") (pintype "bidirectional"))
    )
    (net (code "19") (name "/IN_3") (class "Default")
      (node (ref "IC3") (pin "2") (pinfunction "C_2") (pintype "input"))
      (node (ref "J3") (pin "1") (pinfunction "1_1") (pintype "bidirectional"))
      (node (ref "J3") (pin "2") (pinfunction "2_2") (pintype "bidirectional"))
    )
    (net (code "20") (name "/IN_4") (class "Default")
      (node (ref "IC4") (pin "2") (pinfunction "C_2") (pintype "input"))
      (node (ref "J4") (pin "1") (pinfunction "1_1") (pintype "bidirectional"))
      (node (ref "J4") (pin "2") (pinfunction "2_2") (pintype "bidirectional"))
    )
    (net (code "21") (name "/LCD_BL") (class "Default")
      (node (ref "IC11") (pin "39") (pinfunction "PC8_39") (pintype "bidirectional"))
      (node (ref "P4") (pin "1") (pinfunction "1_1") (pintype "passive"))
    )
    (net (code "22") (name "/LCD_D1") (class "Default")
      (node (ref "IC11") (pin "33") (pinfunction "PB12_33") (pintype "bidirectional"))
      (node (ref "P3") (pin "1") (pinfunction "1_1") (pintype "passive"))
    )
    (net (code "23") (name "/LCD_D2") (class "Default")
      (node (ref "IC11") (pin "34") (pinfunction "PB13_34") (pintype "bidirectional"))
      (node (ref "P3") (pin "2") (pinfunction "2_2") (pintype "passive"))
    )
    (net (code "24") (name "/LCD_D3") (class "Default")
      (node (ref "IC11") (pin "35") (pinfunction "PB14_35") (pintype "bidirectional"))
      (node (ref "P3") (pin "3") (pinfunction "3_3") (pintype "passive"))
    )
    (net (code "25") (name "/LCD_D4") (class "Default")
      (node (ref "IC11") (pin "36") (pinfunction "PB15_36") (pintype "bidirectional"))
      (node (ref "P3") (pin "4") (pinfunction "4_4") (pintype "passive"))
    )
    (net (code "26") (name "/LCD_E") (class "Default")
      (node (ref "IC11") (pin "37") (pinfunction "PC6_37") (pintype "bidirectional"))
      (node (ref "P3") (pin "5") (pinfunction "5_5") (pintype "passive"))
    )
    (net (code "27") (name "/LCD_RS") (class "Default")
      (node (ref "IC11") (pin "38") (pinfunction "PC7_38") (pintype "bidirectional"))
      (node (ref "P3") (pin "6") (pinfunction "6_6") (pintype "passive"))
    )
    (net (code "28") (name "/LED_AUTO") (class "Default")
      (node (ref "IC11") (pin "24") (pinfunction "PC4_24") (pintype "bidirectional"))
      (node (ref "P2") (pin "6") (pinfunction "6_6") (pintype "passive"))
    )
    (net (code "29") (name "/LED_Fault") (class "Default")
      (node (ref "IC11") (pin "28") (pinfunction "PB2/BOOT1_28") (pintype "bidirectional"))
      (node (ref "P2") (pin "5") (pinfunction "5_5") (pintype "passive"))
    )
    (net (code "30") (name "/LED_Healty") (class "Default")
      (node (ref "IC11") (pin "16") (pinfunction "PA2_16") (pintype "bidirectional"))
      (node (ref "P4") (pin "2") (pinfunction "2_2") (pintype "passive"))
    )
    (net (code "31") (name "/LED_MANUAL") (class "Default")
      (node (ref "IC11") (pin "25") (pinfunction "PC5_25") (pintype "bidirectional"))
      (node (ref "P1") (pin "6") (pinfunction "6_6") (pintype "passive"))
    )
    (net (code "32") (name "/LED_OUT1") (class "Default")
      (node (ref "IC11") (pin "26") (pinfunction "PB0_26") (pintype "bidirectional"))
      (node (ref "P2") (pin "3") (pinfunction "3_3") (pintype "passive"))
    )
    (net (code "33") (name "/LED_OUT2") (class "Default")
      (node (ref "IC11") (pin "27") (pinfunction "PB1_27") (pintype "bidirectional"))
      (node (ref "P2") (pin "4") (pinfunction "4_4") (pintype "passive"))
    )
    (net (code "34") (name "/LED_S1") (class "Default")
      (node (ref "IC11") (pin "14") (pinfunction "PA0-WKUP_14") (pintype "bidirectional"))
      (node (ref "P2") (pin "1") (pinfunction "1_1") (pintype "passive"))
    )
    (net (code "35") (name "/LED_S2") (class "Default")
      (node (ref "IC11") (pin "15") (pinfunction "PA1_15") (pintype "bidirectional"))
      (node (ref "P2") (pin "2") (pinfunction "2_2") (pintype "passive"))
    )
    (net (code "36") (name "/OSC1") (class "Default")
      (node (ref "C11") (pin "2") (pinfunction "2_2") (pintype "passive"))
      (node (ref "IC11") (pin "5") (pinfunction "OSC_IN/PD0_5") (pintype "input"))
      (node (ref "Q2") (pin "2") (pinfunction "OSC2_2") (pintype "passive"))
      (node (ref "R16") (pin "1") (pinfunction "1_1") (pintype "passive"))
    )
    (net (code "37") (name "/OSC2") (class "Default")
      (node (ref "C14") (pin "1") (pinfunction "1_1") (pintype "passive"))
      (node (ref "Q2") (pin "1") (pinfunction "OSC1_1") (pintype "passive"))
      (node (ref "R13") (pin "1") (pinfunction "1_1") (pintype "passive"))
      (node (ref "R16") (pin "2") (pinfunction "2_2") (pintype "passive"))
    )
    (net (code "38") (name "/OSC32_1") (class "Default")
      (node (ref "C12") (pin "2") (pinfunction "2_2") (pintype "passive"))
      (node (ref "IC11") (pin "3") (pinfunction "PC14-OSC32_IN_3") (pintype "bidirectional"))
      (node (ref "Q1") (pin "2") (pinfunction "2_2") (pintype "passive"))
    )
    (net (code "39") (name "/OSC32_2") (class "Default")
      (node (ref "C13") (pin "1") (pinfunction "1_1") (pintype "passive"))
      (node (ref "IC11") (pin "4") (pinfunction "PC15-OSC32_OUT_4") (pintype "bidirectional"))
      (node (ref "Q1") (pin "1") (pinfunction "1_1") (pintype "passive"))
    )
    (net (code "40") (name "/RS485_A") (class "Default")
      (node (ref "IC16") (pin "7") (pinfunction "B_7") (pintype "passive"))
      (node (ref "J1") (pin "1") (pinfunction "1_1") (pintype "bidirectional"))
      (node (ref "J1") (pin "2") (pinfunction "2_2") (pintype "bidirectional"))
      (node (ref "MOV1") (pin "1") (pinfunction "1_1") (pintype "passive"))
      (node (ref "MOV2") (pin "2") (pinfunction "2_2") (pintype "passive"))
      (node (ref "R27") (pin "1") (pinfunction "1_1") (pintype "passive"))
      (node (ref "R39") (pin "2") (pinfunction "2_2") (pintype "passive"))
    )
    (net (code "41") (name "/RS485_B") (class "Default")
      (node (ref "IC16") (pin "6") (pinfunction "A_6") (pintype "passive"))
      (node (ref "J1") (pin "3") (pinfunction "3_3") (pintype "bidirectional"))
      (node (ref "J1") (pin "4") (pinfunction "4_4") (pintype "bidirectional"))
      (node (ref "MOV1") (pin "2") (pinfunction "2_2") (pintype "passive"))
      (node (ref "MOV3") (pin "2") (pinfunction "2_2") (pintype "passive"))
      (node (ref "R28") (pin "2") (pinfunction "2_2") (pintype "passive"))
      (node (ref "W2") (pin "1") (pinfunction "1_1") (pintype "bidirectional"))
    )
    (net (code "42") (name "/RS485_Rx") (class "Default")
      (node (ref "IC11") (pin "43") (pinfunction "PA10_43") (pintype "bidirectional"))
      (node (ref "IC13") (pin "5") (pinfunction "VO_5") (pintype "open_collector"))
      (node (ref "R14") (pin "1") (pinfunction "1_1") (pintype "passive"))
    )
    (net (code "43") (name "/RS485_Tx") (class "Default")
      (node (ref "IC11") (pin "42") (pinfunction "PA9_42") (pintype "bidirectional"))
      (node (ref "IC15") (pin "3") (pinfunction "K_3") (pintype "input"))
    )
    (net (code "44") (name "/RS485_direct") (class "Default")
      (node (ref "IC11") (pin "41") (pinfunction "PA8_41") (pintype "bidirectional"))
      (node (ref "IC14") (pin "3") (pinfunction "K_3") (pintype "input"))
      (node (ref "R15") (pin "1") (pinfunction "1_1") (pintype "passive"))
    )
    (net (code "45") (name "/Relay_Fault1") (class "Default")
      (node (ref "J4") (pin "11") (pinfunction "11_11") (pintype "bidirectional"))
      (node (ref "J4") (pin "12") (pinfunction "12_12") (pintype "bidirectional"))
      (node (ref "T4") (pin "2") (pinfunction "E_2") (pintype "passive"))
    )
    (net (code "46") (name "/Relay_Fault2") (class "Default")
      (node (ref "J4") (pin "13") (pinfunction "13_13") (pintype "bidirectional"))
      (node (ref "J4") (pin "14") (pinfunction "14_14") (pintype "bidirectional"))
      (node (ref "T5") (pin "2") (pinfunction "E_2") (pintype "passive"))
    )
    (net (code "47") (name "/Relay_S1") (class "Default")
      (node (ref "J4") (pin "7") (pinfunction "7_7") (pintype "bidirectional"))
      (node (ref "J4") (pin "8") (pinfunction "8_8") (pintype "bidirectional"))
      (node (ref "T2") (pin "2") (pinfunction "E_2") (pintype "passive"))
    )
    (net (code "48") (name "/Relay_S2") (class "Default")
      (node (ref "J4") (pin "10") (pinfunction "10_10") (pintype "bidirectional"))
      (node (ref "J4") (pin "9") (pinfunction "9_9") (pintype "bidirectional"))
      (node (ref "T3") (pin "2") (pinfunction "E_2") (pintype "passive"))
    )
    (net (code "49") (name "/Relayfault1") (class "Default")
      (node (ref "IC11") (pin "17") (pinfunction "PA3_17") (pintype "bidirectional"))
      (node (ref "IC20") (pin "2") (pinfunction "C_2") (pintype "input"))
    )
    (net (code "50") (name "/Relayfault2") (class "Default")
      (node (ref "IC11") (pin "2") (pinfunction "PC13-TAMPER-RTC_2") (pintype "bidirectional"))
      (node (ref "IC21") (pin "2") (pinfunction "C_2") (pintype "input"))
    )
    (net (code "51") (name "/Reset") (class "Default")
      (node (ref "C5") (pin "2") (pinfunction "2_2") (pintype "passive"))
      (node (ref "IC11") (pin "7") (pinfunction "NRST_7") (pintype "bidirectional"))
      (node (ref "R11") (pin "1") (pinfunction "1_1") (pintype "passive"))
    )
    (net (code "52") (name "/S1_Select") (class "Default")
      (node (ref "IC11") (pin "61") (pinfunction "PB8_61") (pintype "bidirectional"))
      (node (ref "IC18") (pin "2") (pinfunction "C_2") (pintype "input"))
    )
    (net (code "53") (name "/S2_Select") (class "Default")
      (node (ref "IC11") (pin "62") (pinfunction "PB9_62") (pintype "bidirectional"))
      (node (ref "IC19") (pin "2") (pinfunction "C_2") (pintype "input"))
    )
    (net (code "54") (name "/SPI1_CS1") (class "Default")
      (node (ref "IC11") (pin "20") (pinfunction "PA4_20") (pintype "bidirectional"))
      (node (ref "J5") (pin "1") (pinfunction "1_1") (pintype "passive"))
    )
    (net (code "55") (name "/SPI1_MISO") (class "Default")
      (node (ref "IC11") (pin "22") (pinfunction "PA6_22") (pintype "bidirectional"))
      (node (ref "J5") (pin "3") (pinfunction "3_3") (pintype "passive"))
    )
    (net (code "56") (name "/SPI1_MOSI") (class "Default")
      (node (ref "IC11") (pin "23") (pinfunction "PA7_23") (pintype "bidirectional"))
      (node (ref "J5") (pin "4") (pinfunction "4_4") (pintype "passive"))
    )
    (net (code "57") (name "/SPI1_SCK") (class "Default")
      (node (ref "IC11") (pin "21") (pinfunction "PA5_21") (pintype "bidirectional"))
      (node (ref "J5") (pin "2") (pinfunction "2_2") (pintype "passive"))
    )
    (net (code "58") (name "/SPI2_CLK") (class "Default")
      (node (ref "IC11") (pin "29") (pinfunction "PB10_29") (pintype "bidirectional"))
      (node (ref "J5") (pin "7") (pinfunction "7_7") (pintype "passive"))
    )
    (net (code "59") (name "/SPI2_CS") (class "Default")
      (node (ref "IC11") (pin "30") (pinfunction "PB11_30") (pintype "bidirectional"))
      (node (ref "J5") (pin "6") (pinfunction "6_6") (pintype "passive"))
    )
    (net (code "60") (name "/SPI2_MISO") (class "Default")
      (node (ref "IC11") (pin "10") (pinfunction "PC2_10") (pintype "bidirectional"))
      (node (ref "J5") (pin "8") (pinfunction "8_8") (pintype "passive"))
    )
    (net (code "61") (name "/SPI2_MOSI") (class "Default")
      (node (ref "IC11") (pin "11") (pinfunction "PC3_11") (pintype "bidirectional"))
      (node (ref "J5") (pin "9") (pinfunction "9_9") (pintype "passive"))
    )
    (net (code "62") (name "/SWCLK") (class "Default")
      (node (ref "IC11") (pin "49") (pinfunction "PA14/JTCK/SWCLK_49") (pintype "bidirectional"))
      (node (ref "W1") (pin "2") (pinfunction "2_2") (pintype "bidirectional"))
    )
    (net (code "63") (name "/SWDIO") (class "Default")
      (node (ref "IC11") (pin "46") (pinfunction "PA13/JTMS/SWDIO_46") (pintype "bidirectional"))
      (node (ref "W1") (pin "4") (pinfunction "4_4") (pintype "bidirectional"))
    )
    (net (code "64") (name "/UP_btn") (class "Default")
      (node (ref "IC8") (pin "2") (pinfunction "C_2") (pintype "input"))
      (node (ref "J3") (pin "10") (pinfunction "10_10") (pintype "bidirectional"))
      (node (ref "J3") (pin "9") (pinfunction "9_9") (pintype "bidirectional"))
    )
    (net (code "65") (name "/USB_DM") (class "Default")
      (node (ref "IC11") (pin "44") (pinfunction "PA11_44") (pintype "bidirectional"))
      (node (ref "R5") (pin "1") (pinfunction "1_1") (pintype "passive"))
    )
    (net (code "66") (name "/USB_DP") (class "Default")
      (node (ref "IC11") (pin "45") (pinfunction "PA12_45") (pintype "bidirectional"))
      (node (ref "R6") (pin "1") (pinfunction "1_1") (pintype "passive"))
    )
    (net (code "67") (name "/man_auto") (class "Default")
      (node (ref "IC11") (pin "59") (pinfunction "PB7_59") (pintype "bidirectional"))
      (node (ref "IC6") (pin "4") (pinfunction "C_4") (pintype "open_collector"))
      (node (ref "P4") (pin "4") (pinfunction "4_4") (pintype "passive"))
    )
    (net (code "68") (name "D3.3V") (class "Default")
      (node (ref "C3") (pin "1") (pinfunction "1_1") (pintype "passive"))
      (node (ref "C4") (pin "1") (pinfunction "1_1") (pintype "passive"))
      (node (ref "IC13") (pin "6") (pinfunction "VCC_6") (pintype "power_in"))
      (node (ref "IC5") (pin "2") (pinfunction "OUT_2") (pintype "power_in"))
      (node (ref "IC5") (pin "4") (pinfunction "OUT_4") (pintype "power_in"))
      (node (ref "J1") (pin "10") (pinfunction "10_10") (pintype "bidirectional"))
      (node (ref "J1") (pin "9") (pinfunction "9_9") (pintype "bidirectional"))
      (node (ref "J2") (pin "1") (pinfunction "VBUS_1") (pintype "bidirectional"))
      (node (ref "L1") (pin "1") (pinfunction "1_1") (pintype "passive"))
      (node (ref "P1") (pin "2") (pinfunction "2_2") (pintype "passive"))
      (node (ref "P1") (pin "4") (pinfunction "4_4") (pintype "passive"))
      (node (ref "R14") (pin "2") (pinfunction "2_2") (pintype "passive"))
      (node (ref "R15") (pin "2") (pinfunction "2_2") (pintype "passive"))
      (node (ref "R17") (pin "2") (pinfunction "2_2") (pintype "passive"))
      (node (ref "R18") (pin "2") (pinfunction "2_2") (pintype "passive"))
      (node (ref "R22") (pin "2") (pinfunction "2_2") (pintype "passive"))
      (node (ref "R23") (pin "2") (pinfunction "2_2") (pintype "passive"))
      (node (ref "R24") (pin "2") (pinfunction "2_2") (pintype "passive"))
      (node (ref "R25") (pin "2") (pinfunction "2_2") (pintype "passive"))
      (node (ref "R26") (pin "2") (pinfunction "2_2") (pintype "passive"))
    )
    (net (code "69") (name "GND") (class "Default")
      (node (ref "B2") (pin "1") (pinfunction "1_1") (pintype "bidirectional"))
      (node (ref "C1") (pin "2") (pinfunction "2_2") (pintype "passive"))
      (node (ref "C10") (pin "2") (pinfunction "2_2") (pintype "passive"))
      (node (ref "C11") (pin "1") (pinfunction "1_1") (pintype "passive"))
      (node (ref "C12") (pin "1") (pinfunction "1_1") (pintype "passive"))
      (node (ref "C13") (pin "2") (pinfunction "2_2") (pintype "passive"))
      (node (ref "C14") (pin "2") (pinfunction "2_2") (pintype "passive"))
      (node (ref "C2") (pin "2") (pinfunction "2_2") (pintype "passive"))
      (node (ref "C3") (pin "2") (pinfunction "2_2") (pintype "passive"))
      (node (ref "C4") (pin "2") (pinfunction "2_2") (pintype "passive"))
      (node (ref "C5") (pin "1") (pinfunction "1_1") (pintype "passive"))
      (node (ref "C6") (pin "2") (pinfunction "2_2") (pintype "passive"))
      (node (ref "C7") (pin "2") (pinfunction "2_2") (pintype "passive"))
      (node (ref "C8") (pin "2") (pinfunction "2_2") (pintype "passive"))
      (node (ref "C9") (pin "2") (pinfunction "2_2") (pintype "passive"))
      (node (ref "IC1") (pin "3") (pinfunction "E_3") (pintype "open_emitter"))
      (node (ref "IC10") (pin "2") (pinfunction "2_2") (pintype "passive"))
      (node (ref "IC11") (pin "12") (pinfunction "VSSA_12") (pintype "power_in"))
      (node (ref "IC11") (pin "18") (pinfunction "VSS_4_18") (pintype "power_in"))
      (node (ref "IC11") (pin "31") (pinfunction "VSS_1_31") (pintype "power_in"))
      (node (ref "IC11") (pin "47") (pinfunction "VSS_2_47") (pintype "power_in"))
      (node (ref "IC11") (pin "63") (pinfunction "VSS_3_63") (pintype "power_in"))
      (node (ref "IC12") (pin "1") (pinfunction "-Vin_1") (pintype "input"))
      (node (ref "IC13") (pin "4") (pinfunction "GND_4") (pintype "power_in"))
      (node (ref "IC18") (pin "3") (pinfunction "E_3") (pintype "open_emitter"))
      (node (ref "IC19") (pin "3") (pinfunction "E_3") (pintype "open_emitter"))
      (node (ref "IC2") (pin "3") (pinfunction "E_3") (pintype "open_emitter"))
      (node (ref "IC20") (pin "3") (pinfunction "E_3") (pintype "open_emitter"))
      (node (ref "IC21") (pin "3") (pinfunction "E_3") (pintype "open_emitter"))
      (node (ref "IC3") (pin "3") (pinfunction "E_3") (pintype "open_emitter"))
      (node (ref "IC4") (pin "3") (pinfunction "E_3") (pintype "open_emitter"))
      (node (ref "IC5") (pin "1") (pinfunction "ADJ_1") (pintype "power_in"))
      (node (ref "IC6") (pin "3") (pinfunction "E_3") (pintype "open_emitter"))
      (node (ref "IC7") (pin "3") (pinfunction "E_3") (pintype "open_emitter"))
      (node (ref "IC8") (pin "3") (pinfunction "E_3") (pintype "open_emitter"))
      (node (ref "IC9") (pin "3") (pinfunction "E_3") (pintype "open_emitter"))
      (node (ref "J1") (pin "5") (pinfunction "5_5") (pintype "bidirectional"))
      (node (ref "J1") (pin "6") (pinfunction "6_6") (pintype "bidirectional"))
      (node (ref "J1") (pin "7") (pinfunction "7_7") (pintype "bidirectional"))
      (node (ref "J1") (pin "8") (pinfunction "8_8") (pintype "bidirectional"))
      (node (ref "J2") (pin "5") (pinfunction "GND_5") (pintype "bidirectional"))
      (node (ref "J2") (pin "6") (pinfunction "SH_6") (pintype "power_in"))
      (node (ref "J5") (pin "12") (pinfunction "12_12") (pintype "passive"))
      (node (ref "J5") (pin "14") (pinfunction "14_14") (pintype "passive"))
      (node (ref "P1") (pin "1") (pinfunction "1_1") (pintype "passive"))
      (node (ref "P1") (pin "3") (pinfunction "3_3") (pintype "passive"))
      (node (ref "P1") (pin "5") (pinfunction "5_5") (pintype "passive"))
      (node (ref "R12") (pin "1") (pinfunction "1_1") (pintype "passive"))
      (node (ref "T2") (pin "3") (pinfunction "C_3") (pintype "passive"))
      (node (ref "T3") (pin "3") (pinfunction "C_3") (pintype "passive"))
      (node (ref "T4") (pin "3") (pinfunction "C_3") (pintype "passive"))
      (node (ref "T5") (pin "3") (pinfunction "C_3") (pintype "passive"))
      (node (ref "W1") (pin "3") (pinfunction "3_3") (pintype "bidirectional"))
    )
    (net (code "70") (name "GND24") (class "Default")
      (node (ref "IC17") (pin "3") (pinfunction "E_3") (pintype "open_emitter"))
      (node (ref "T1") (pin "3") (pinfunction "C_3") (pintype "passive"))
    )
    (net (code "71") (name "GND485") (class "Default")
      (node (ref "C15") (pin "2") (pinfunction "2_2") (pintype "passive"))
      (node (ref "C16") (pin "2") (pinfunction "2_2") (pintype "passive"))
      (node (ref "IC12") (pin "7") (pinfunction "-Vout_7") (pintype "power_in"))
      (node (ref "IC14") (pin "4") (pinfunction "GND_4") (pintype "power_in"))
      (node (ref "IC15") (pin "4") (pinfunction "GND_4") (pintype "power_in"))
      (node (ref "IC16") (pin "5") (pinfunction "GND_5") (pintype "passive"))
      (node (ref "MOV2") (pin "1") (pinfunction "1_1") (pintype "passive"))
      (node (ref "MOV3") (pin "1") (pinfunction "1_1") (pintype "passive"))
      (node (ref "R27") (pin "2") (pinfunction "2_2") (pintype "passive"))
    )
    (net (code "72") (name "MCU_VCC") (class "Default")
      (node (ref "C10") (pin "1") (pinfunction "1_1") (pintype "passive"))
      (node (ref "C6") (pin "1") (pinfunction "1_1") (pintype "passive"))
      (node (ref "C7") (pin "1") (pinfunction "1_1") (pintype "passive"))
      (node (ref "C8") (pin "1") (pinfunction "1_1") (pintype "passive"))
      (node (ref "C9") (pin "1") (pinfunction "1_1") (pintype "passive"))
      (node (ref "IC11") (pin "13") (pinfunction "VDDA_13") (pintype "power_in"))
      (node (ref "IC11") (pin "19") (pinfunction "VDD_4_19") (pintype "power_in"))
      (node (ref "IC11") (pin "32") (pinfunction "VDD_1_32") (pintype "power_in"))
      (node (ref "IC11") (pin "48") (pinfunction "VDD_2_48") (pintype "power_in"))
      (node (ref "IC11") (pin "64") (pinfunction "VDD_3_64") (pintype "power_in"))
      (node (ref "L1") (pin "2") (pinfunction "2_2") (pintype "passive"))
      (node (ref "R11") (pin "2") (pinfunction "2_2") (pintype "passive"))
      (node (ref "W1") (pin "1") (pinfunction "1_1") (pintype "bidirectional"))
    )
    (net (code "73") (name "Net-(IC1-A)") (class "Default")
      (node (ref "IC1") (pin "1") (pinfunction "A_1") (pintype "input"))
      (node (ref "R1") (pin "1") (pinfunction "1_1") (pintype "passive"))
    )
    (net (code "74") (name "Net-(IC2-A)") (class "Default")
      (node (ref "IC2") (pin "1") (pinfunction "A_1") (pintype "input"))
      (node (ref "R2") (pin "1") (pinfunction "1_1") (pintype "passive"))
    )
    (net (code "75") (name "Net-(IC3-A)") (class "Default")
      (node (ref "IC3") (pin "1") (pinfunction "A_1") (pintype "input"))
      (node (ref "R3") (pin "1") (pinfunction "1_1") (pintype "passive"))
    )
    (net (code "76") (name "Net-(IC4-A)") (class "Default")
      (node (ref "IC4") (pin "1") (pinfunction "A_1") (pintype "input"))
      (node (ref "R4") (pin "1") (pinfunction "1_1") (pintype "passive"))
    )
    (net (code "77") (name "Net-(IC6-A)") (class "Default")
      (node (ref "IC6") (pin "1") (pinfunction "A_1") (pintype "input"))
      (node (ref "R7") (pin "1") (pinfunction "1_1") (pintype "passive"))
    )
    (net (code "78") (name "Net-(IC7-A)") (class "Default")
      (node (ref "IC7") (pin "1") (pinfunction "A_1") (pintype "input"))
      (node (ref "R8") (pin "1") (pinfunction "1_1") (pintype "passive"))
    )
    (net (code "79") (name "Net-(IC8-A)") (class "Default")
      (node (ref "IC8") (pin "1") (pinfunction "A_1") (pintype "input"))
      (node (ref "R9") (pin "1") (pinfunction "1_1") (pintype "passive"))
    )
    (net (code "80") (name "Net-(IC9-A)") (class "Default")
      (node (ref "IC9") (pin "1") (pinfunction "A_1") (pintype "input"))
      (node (ref "R10") (pin "1") (pinfunction "1_1") (pintype "passive"))
    )
    (net (code "81") (name "Net-(IC11-BOOT0)") (class "Default")
      (node (ref "IC11") (pin "60") (pinfunction "BOOT0_60") (pintype "input"))
      (node (ref "R12") (pin "2") (pinfunction "2_2") (pintype "passive"))
    )
    (net (code "82") (name "Net-(IC11-OSC_OUT{slash}PD1)") (class "Default")
      (node (ref "IC11") (pin "6") (pinfunction "OSC_OUT/PD1_6") (pintype "output"))
      (node (ref "R13") (pin "2") (pinfunction "2_2") (pintype "passive"))
    )
    (net (code "83") (name "Net-(IC11-VBAT)") (class "Default")
      (node (ref "IC10") (pin "1") (pinfunction "1_1") (pintype "passive"))
      (node (ref "IC10") (pin "3") (pinfunction "3_3") (pintype "passive"))
      (node (ref "IC11") (pin "1") (pinfunction "VBAT_1") (pintype "power_in"))
    )
    (net (code "84") (name "Net-(IC13-A)") (class "Default")
      (node (ref "IC13") (pin "1") (pinfunction "A_1") (pintype "input"))
      (node (ref "R19") (pin "1") (pinfunction "1_1") (pintype "passive"))
    )
    (net (code "85") (name "Net-(IC13-K)") (class "Default")
      (node (ref "IC13") (pin "3") (pinfunction "K_3") (pintype "input"))
      (node (ref "IC16") (pin "1") (pinfunction "R_1") (pintype "passive"))
    )
    (net (code "86") (name "Net-(IC14-A)") (class "Default")
      (node (ref "IC14") (pin "1") (pinfunction "A_1") (pintype "input"))
      (node (ref "R17") (pin "1") (pinfunction "1_1") (pintype "passive"))
    )
    (net (code "87") (name "Net-(IC14-VO)") (class "Default")
      (node (ref "IC14") (pin "5") (pinfunction "VO_5") (pintype "open_collector"))
      (node (ref "IC16") (pin "2") (pinfunction "~{RE}_2") (pintype "passive"))
      (node (ref "IC16") (pin "3") (pinfunction "DE_3") (pintype "passive"))
      (node (ref "R20") (pin "1") (pinfunction "1_1") (pintype "passive"))
    )
    (net (code "88") (name "Net-(IC15-A)") (class "Default")
      (node (ref "IC15") (pin "1") (pinfunction "A_1") (pintype "input"))
      (node (ref "R18") (pin "1") (pinfunction "1_1") (pintype "passive"))
    )
    (net (code "89") (name "Net-(IC15-VO)") (class "Default")
      (node (ref "IC15") (pin "5") (pinfunction "VO_5") (pintype "open_collector"))
      (node (ref "IC16") (pin "4") (pinfunction "D_4") (pintype "passive"))
      (node (ref "R21") (pin "1") (pinfunction "1_1") (pintype "passive"))
    )
    (net (code "90") (name "Net-(IC17-A)") (class "Default")
      (node (ref "IC17") (pin "1") (pinfunction "A_1") (pintype "input"))
      (node (ref "R22") (pin "1") (pinfunction "1_1") (pintype "passive"))
    )
    (net (code "91") (name "Net-(IC17-C-Pad4)") (class "Default")
      (node (ref "IC17") (pin "4") (pinfunction "C_4") (pintype "open_collector"))
      (node (ref "R29") (pin "1") (pinfunction "1_1") (pintype "passive"))
      (node (ref "R30") (pin "2") (pinfunction "2_2") (pintype "passive"))
    )
    (net (code "92") (name "Net-(IC18-A)") (class "Default")
      (node (ref "IC18") (pin "1") (pinfunction "A_1") (pintype "input"))
      (node (ref "R23") (pin "1") (pinfunction "1_1") (pintype "passive"))
    )
    (net (code "93") (name "Net-(IC18-C-Pad4)") (class "Default")
      (node (ref "IC18") (pin "4") (pinfunction "C_4") (pintype "open_collector"))
      (node (ref "R31") (pin "1") (pinfunction "1_1") (pintype "passive"))
      (node (ref "R35") (pin "2") (pinfunction "2_2") (pintype "passive"))
    )
    (net (code "94") (name "Net-(IC19-A)") (class "Default")
      (node (ref "IC19") (pin "1") (pinfunction "A_1") (pintype "input"))
      (node (ref "R24") (pin "1") (pinfunction "1_1") (pintype "passive"))
    )
    (net (code "95") (name "Net-(IC19-C-Pad4)") (class "Default")
      (node (ref "IC19") (pin "4") (pinfunction "C_4") (pintype "open_collector"))
      (node (ref "R32") (pin "1") (pinfunction "1_1") (pintype "passive"))
      (node (ref "R36") (pin "2") (pinfunction "2_2") (pintype "passive"))
    )
    (net (code "96") (name "Net-(IC20-A)") (class "Default")
      (node (ref "IC20") (pin "1") (pinfunction "A_1") (pintype "input"))
      (node (ref "R25") (pin "1") (pinfunction "1_1") (pintype "passive"))
    )
    (net (code "97") (name "Net-(IC20-C-Pad4)") (class "Default")
      (node (ref "IC20") (pin "4") (pinfunction "C_4") (pintype "open_collector"))
      (node (ref "R33") (pin "1") (pinfunction "1_1") (pintype "passive"))
      (node (ref "R37") (pin "2") (pinfunction "2_2") (pintype "passive"))
    )
    (net (code "98") (name "Net-(IC21-A)") (class "Default")
      (node (ref "IC21") (pin "1") (pinfunction "A_1") (pintype "input"))
      (node (ref "R26") (pin "1") (pinfunction "1_1") (pintype "passive"))
    )
    (net (code "99") (name "Net-(IC21-C-Pad4)") (class "Default")
      (node (ref "IC21") (pin "4") (pinfunction "C_4") (pintype "open_collector"))
      (node (ref "R34") (pin "1") (pinfunction "1_1") (pintype "passive"))
      (node (ref "R38") (pin "2") (pinfunction "2_2") (pintype "passive"))
    )
    (net (code "100") (name "Net-(J2-+D)") (class "Default")
      (node (ref "J2") (pin "3") (pinfunction "+D_3") (pintype "bidirectional"))
      (node (ref "R6") (pin "2") (pinfunction "2_2") (pintype "passive"))
    )
    (net (code "101") (name "Net-(J2--D)") (class "Default")
      (node (ref "J2") (pin "2") (pinfunction "-D_2") (pintype "bidirectional"))
      (node (ref "R5") (pin "2") (pinfunction "2_2") (pintype "passive"))
    )
    (net (code "102") (name "Net-(LS1--)") (class "Default")
      (node (ref "LS1") (pin "2") (pinfunction "-_2") (pintype "passive"))
      (node (ref "T1") (pin "2") (pinfunction "E_2") (pintype "passive"))
    )
    (net (code "103") (name "Net-(R39-Pad1)") (class "Default")
      (node (ref "R39") (pin "1") (pinfunction "1_1") (pintype "passive"))
      (node (ref "W2") (pin "2") (pinfunction "2_2") (pintype "bidirectional"))
    )
    (net (code "104") (name "Net-(T1-B)") (class "Default")
      (node (ref "R30") (pin "1") (pinfunction "1_1") (pintype "passive"))
      (node (ref "T1") (pin "1") (pinfunction "B_1") (pintype "passive"))
    )
    (net (code "105") (name "Net-(T2-B)") (class "Default")
      (node (ref "R35") (pin "1") (pinfunction "1_1") (pintype "passive"))
      (node (ref "T2") (pin "1") (pinfunction "B_1") (pintype "passive"))
    )
    (net (code "106") (name "Net-(T3-B)") (class "Default")
      (node (ref "R36") (pin "1") (pinfunction "1_1") (pintype "passive"))
      (node (ref "T3") (pin "1") (pinfunction "B_1") (pintype "passive"))
    )
    (net (code "107") (name "Net-(T4-B)") (class "Default")
      (node (ref "R37") (pin "1") (pinfunction "1_1") (pintype "passive"))
      (node (ref "T4") (pin "1") (pinfunction "B_1") (pintype "passive"))
    )
    (net (code "108") (name "Net-(T5-B)") (class "Default")
      (node (ref "R38") (pin "1") (pinfunction "1_1") (pintype "passive"))
      (node (ref "T5") (pin "1") (pinfunction "B_1") (pintype "passive"))
    )
    (net (code "109") (name "VCC485") (class "Default")
      (node (ref "C15") (pin "1") (pinfunction "1_1") (pintype "passive"))
      (node (ref "C16") (pin "1") (pinfunction "1_1") (pintype "passive"))
      (node (ref "IC12") (pin "8") (pinfunction "+Vout_8") (pintype "power_in"))
      (node (ref "IC14") (pin "6") (pinfunction "VCC_6") (pintype "power_in"))
      (node (ref "IC15") (pin "6") (pinfunction "VCC_6") (pintype "power_in"))
      (node (ref "IC16") (pin "8") (pinfunction "VCC_8") (pintype "passive"))
      (node (ref "R19") (pin "2") (pinfunction "2_2") (pintype "passive"))
      (node (ref "R20") (pin "2") (pinfunction "2_2") (pintype "passive"))
      (node (ref "R21") (pin "2") (pinfunction "2_2") (pintype "passive"))
      (node (ref "R28") (pin "1") (pinfunction "1_1") (pintype "passive"))
    )
    (net (code "110") (name "unconnected-(J2-ID-Pad4)") (class "Default")
      (node (ref "J2") (pin "4") (pinfunction "ID_4") (pintype "passive"))
    )
    (net (code "111") (name "unconnected-(J4-Pad3)") (class "Default")
      (node (ref "J4") (pin "3") (pinfunction "3_3") (pintype "bidirectional"))
    )
    (net (code "112") (name "unconnected-(J4-Pad4)") (class "Default")
      (node (ref "J4") (pin "4") (pinfunction "4_4") (pintype "bidirectional"))
    )
    (net (code "113") (name "unconnected-(J4-Pad5)") (class "Default")
      (node (ref "J4") (pin "5") (pinfunction "5_5") (pintype "bidirectional"))
    )
    (net (code "114") (name "unconnected-(J4-Pad6)") (class "Default")
      (node (ref "J4") (pin "6") (pinfunction "6_6") (pintype "bidirectional"))
    )
  )
)
